# 03_-_SCHEMATIC.net
KiCad netlist of a schematic drawn in Altium Designer
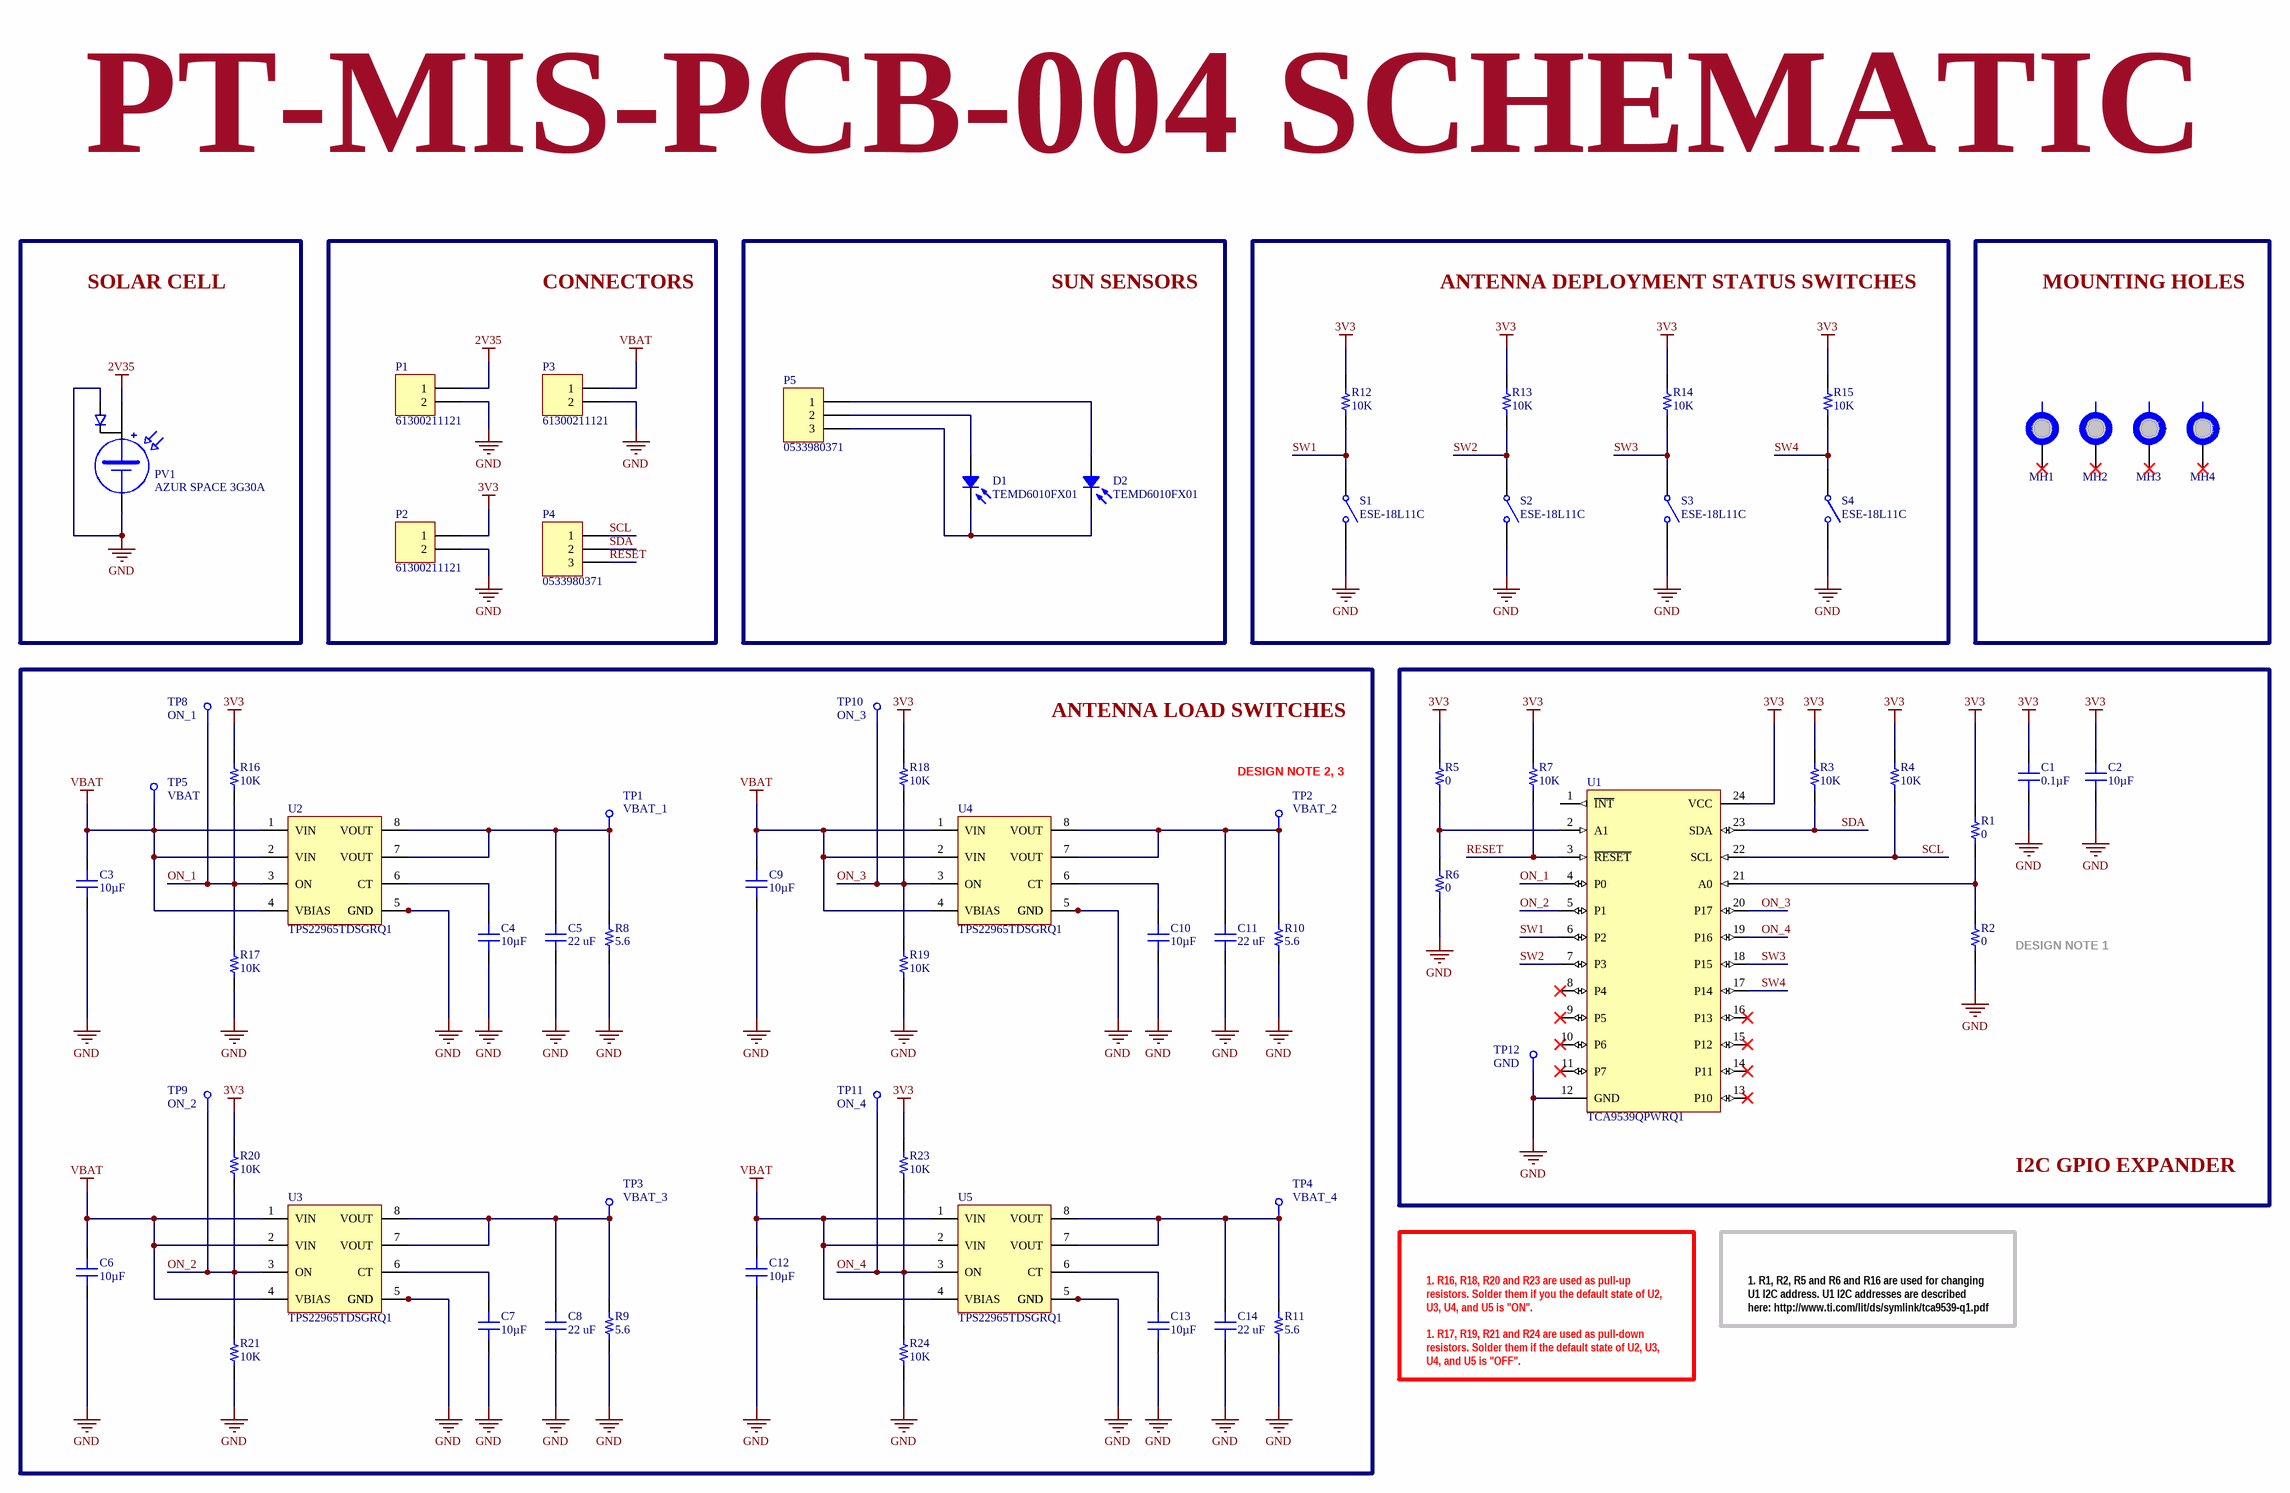
[diagram p0: [03] - SCHEMATIC.SchDoc]

(export (version "E")
  (design (tool "Eeschema 10.0.6"))
  (components
    (comp (ref "C1")
      (value "0.1µF")
      (footprint "CAP 0805/2012")
      (description "Multilayer Ceramic Capacitors MLCC - SMD/SMT 25volts 0.1uF Y5V -20+80%")
      (fields
        (field (name "MANUFACTURER") "KEMET")
        (field (name "MANUFACTURER PART NUMBER") "C0805C104Z3VACTU")
      )
      (libsource (lib "UVG") (part "C0805C104Z3VACTU"))
    )
    (comp (ref "C2")
      (value "LMK212BJ106KG-T")
      (footprint "CAP 0805/2012")
      (description "CAP CER 10UF 10V X5R 0805")
      (fields
        (field (name "MANUFACTURER") "Taiyo Yuden")
        (field (name "PCN PART NUMBER") "X5R, X7R Dielectrics 23/Jan/2008")
        (field (name "CAPACITANCE") "10µF")
      )
      (libsource (lib "UVG") (part "LMK212BJ106KG-T"))
    )
    (comp (ref "C3")
      (value "LMK212BJ106KG-T")
      (footprint "CAP 0805/2012")
      (description "CAP CER 10UF 10V X5R 0805")
      (fields
        (field (name "MANUFACTURER") "Taiyo Yuden")
        (field (name "PCN PART NUMBER") "X5R, X7R Dielectrics 23/Jan/2008")
        (field (name "CAPACITANCE") "10µF")
      )
      (libsource (lib "UVG") (part "LMK212BJ106KG-T"))
    )
    (comp (ref "C4")
      (value "LMK212BJ106KG-T")
      (footprint "CAP 0805/2012")
      (description "CAP CER 10UF 10V X5R 0805")
      (fields
        (field (name "MANUFACTURER") "Taiyo Yuden")
        (field (name "PCN PART NUMBER") "X5R, X7R Dielectrics 23/Jan/2008")
        (field (name "CAPACITANCE") "10µF")
      )
      (libsource (lib "UVG") (part "LMK212BJ106KG-T"))
    )
    (comp (ref "C5")
      (value "GRM21BR61E226ME44L")
      (footprint "CAP 0805/2012")
      (fields
        (field (name "MANUFACTURER") "Murata")
        (field (name "CAPACITANCE") "22 uF")
        (field (name "TOLERANCE") "20 %")
      )
      (libsource (lib "UVG") (part "GRM21BR61E226ME44L"))
    )
    (comp (ref "C6")
      (value "LMK212BJ106KG-T")
      (footprint "CAP 0805/2012")
      (description "CAP CER 10UF 10V X5R 0805")
      (fields
        (field (name "MANUFACTURER") "Taiyo Yuden")
        (field (name "PCN PART NUMBER") "X5R, X7R Dielectrics 23/Jan/2008")
        (field (name "CAPACITANCE") "10µF")
      )
      (libsource (lib "UVG") (part "LMK212BJ106KG-T"))
    )
    (comp (ref "C7")
      (value "LMK212BJ106KG-T")
      (footprint "CAP 0805/2012")
      (description "CAP CER 10UF 10V X5R 0805")
      (fields
        (field (name "MANUFACTURER") "Taiyo Yuden")
        (field (name "PCN PART NUMBER") "X5R, X7R Dielectrics 23/Jan/2008")
        (field (name "CAPACITANCE") "10µF")
      )
      (libsource (lib "UVG") (part "LMK212BJ106KG-T"))
    )
    (comp (ref "C8")
      (value "GRM21BR61E226ME44L")
      (footprint "CAP 0805/2012")
      (fields
        (field (name "MANUFACTURER") "Murata")
        (field (name "CAPACITANCE") "22 uF")
        (field (name "TOLERANCE") "20 %")
      )
      (libsource (lib "UVG") (part "GRM21BR61E226ME44L"))
    )
    (comp (ref "C9")
      (value "LMK212BJ106KG-T")
      (footprint "CAP 0805/2012")
      (description "CAP CER 10UF 10V X5R 0805")
      (fields
        (field (name "MANUFACTURER") "Taiyo Yuden")
        (field (name "PCN PART NUMBER") "X5R, X7R Dielectrics 23/Jan/2008")
        (field (name "CAPACITANCE") "10µF")
      )
      (libsource (lib "UVG") (part "LMK212BJ106KG-T"))
    )
    (comp (ref "C10")
      (value "LMK212BJ106KG-T")
      (footprint "CAP 0805/2012")
      (description "CAP CER 10UF 10V X5R 0805")
      (fields
        (field (name "MANUFACTURER") "Taiyo Yuden")
        (field (name "PCN PART NUMBER") "X5R, X7R Dielectrics 23/Jan/2008")
        (field (name "CAPACITANCE") "10µF")
      )
      (libsource (lib "UVG") (part "LMK212BJ106KG-T"))
    )
    (comp (ref "C11")
      (value "GRM21BR61E226ME44L")
      (footprint "CAP 0805/2012")
      (fields
        (field (name "MANUFACTURER") "Murata")
        (field (name "CAPACITANCE") "22 uF")
        (field (name "TOLERANCE") "20 %")
      )
      (libsource (lib "UVG") (part "GRM21BR61E226ME44L"))
    )
    (comp (ref "C12")
      (value "LMK212BJ106KG-T")
      (footprint "CAP 0805/2012")
      (description "CAP CER 10UF 10V X5R 0805")
      (fields
        (field (name "MANUFACTURER") "Taiyo Yuden")
        (field (name "PCN PART NUMBER") "X5R, X7R Dielectrics 23/Jan/2008")
        (field (name "CAPACITANCE") "10µF")
      )
      (libsource (lib "UVG") (part "LMK212BJ106KG-T"))
    )
    (comp (ref "C13")
      (value "LMK212BJ106KG-T")
      (footprint "CAP 0805/2012")
      (description "CAP CER 10UF 10V X5R 0805")
      (fields
        (field (name "MANUFACTURER") "Taiyo Yuden")
        (field (name "PCN PART NUMBER") "X5R, X7R Dielectrics 23/Jan/2008")
        (field (name "CAPACITANCE") "10µF")
      )
      (libsource (lib "UVG") (part "LMK212BJ106KG-T"))
    )
    (comp (ref "C14")
      (value "GRM21BR61E226ME44L")
      (footprint "CAP 0805/2012")
      (fields
        (field (name "MANUFACTURER") "Murata")
        (field (name "CAPACITANCE") "22 uF")
        (field (name "TOLERANCE") "20 %")
      )
      (libsource (lib "UVG") (part "GRM21BR61E226ME44L"))
    )
    (comp (ref "D1")
      (value "TEMD6010FX01")
      (footprint "TEMD6010FX01")
      (description "Ambient Light Sensor")
      (fields (field (name "MANUFACTURER") "Vishay Semiconductors"))
      (libsource (lib "UVG") (part "TEMD6010FX01"))
    )
    (comp (ref "D2")
      (value "TEMD6010FX01")
      (footprint "TEMD6010FX01")
      (description "Ambient Light Sensor")
      (fields (field (name "MANUFACTURER") "Vishay Semiconductors"))
      (libsource (lib "UVG") (part "TEMD6010FX01"))
    )
    (comp (ref "MH1")
      (value "MH_3.8MMNC_2.5MMD")
      (footprint "MH_3.8MMNC_2.5MMD_NON_COPPER_NPTH")
      (description "Mounting Hole 3.8mm Diameter (Non Copper), 2.5mm Drill NPTH")
      (libsource (lib "UVG") (part "MH_3.8MMNC_2MMD"))
    )
    (comp (ref "MH2")
      (value "MH_3.8MMNC_2.5MMD")
      (footprint "MH_3.8MMNC_2.5MMD_NON_COPPER_NPTH")
      (description "Mounting Hole 3.8mm Diameter (Non Copper), 2.5mm Drill NPTH")
      (libsource (lib "UVG") (part "MH_3.8MMNC_2MMD"))
    )
    (comp (ref "MH3")
      (value "MH_3.8MMNC_2.5MMD")
      (footprint "MH_3.8MMNC_2.5MMD_NON_COPPER_NPTH")
      (description "Mounting Hole 3.8mm Diameter (Non Copper), 2.5mm Drill NPTH")
      (libsource (lib "UVG") (part "MH_3.8MMNC_2MMD"))
    )
    (comp (ref "MH4")
      (value "MH_3.8MMNC_2.5MMD")
      (footprint "MH_3.8MMNC_2.5MMD_NON_COPPER_NPTH")
      (description "Mounting Hole 3.8mm Diameter (Non Copper), 2.5mm Drill NPTH")
      (libsource (lib "UVG") (part "MH_3.8MMNC_2MMD"))
    )
    (comp (ref "P1")
      (value "61300211121")
      (footprint "61300211121")
      (description "Headers & Wire Housings WR-PHD 2.54mm Header 2P THT")
      (fields (field (name "MANUFACTURER") "Wurth Electronics"))
      (libsource (lib "UVG") (part "61300211121"))
    )
    (comp (ref "P2")
      (value "61300211121")
      (footprint "61300211121")
      (description "Headers & Wire Housings WR-PHD 2.54mm Header 2P THT")
      (fields (field (name "MANUFACTURER") "Wurth Electronics"))
      (libsource (lib "UVG") (part "61300211121"))
    )
    (comp (ref "P3")
      (value "61300211121")
      (footprint "61300211121")
      (description "Headers & Wire Housings WR-PHD 2.54mm Header 2P THT")
      (fields (field (name "MANUFACTURER") "Wurth Electronics"))
      (libsource (lib "UVG") (part "61300211121"))
    )
    (comp (ref "P4")
      (value "0533980371")
      (footprint "0533980371")
      (description "3 Positions Header, Shrouded Connector 0.049\" (1.25mm) Surface Mount, Vertical Tin")
      (fields (field (name "MANUFACTURER") "Molex"))
      (libsource (lib "UVG") (part "0533980371"))
    )
    (comp (ref "P5")
      (value "0533980371")
      (footprint "0533980371")
      (description "3 Positions Header, Shrouded Connector 0.049\" (1.25mm) Surface Mount, Vertical Tin")
      (fields (field (name "MANUFACTURER") "Molex"))
      (libsource (lib "UVG") (part "0533980371"))
    )
    (comp (ref "PV1")
      (value "AZUR SPACE 3G30A")
      (footprint "AZUR SPACE 3G30A")
      (description "30% Triple Junction GaAs Solar Cell Assembly")
      (libsource (lib "UVG") (part "AZUR SPACE 3G30A"))
    )
    (comp (ref "R1")
      (value "0")
      (footprint "RES 0805/2012")
      (description "YAGEO         RC0805JR-070RL             RES, THICK FILM, 0R, 0.125W, 0805")
      (fields
        (field (name "MANUFACTURER") "Yageo")
        (field (name "MANUFACTURER PART NUMBER") "RC0805JR-070RL")
      )
      (libsource (lib "UVG") (part "RC0805JR-070RL"))
    )
    (comp (ref "R2")
      (value "0")
      (footprint "RES 0805/2012")
      (description "YAGEO         RC0805JR-070RL             RES, THICK FILM, 0R, 0.125W, 0805")
      (fields
        (field (name "MANUFACTURER") "Yageo")
        (field (name "MANUFACTURER PART NUMBER") "RC0805JR-070RL")
      )
      (libsource (lib "UVG") (part "RC0805JR-070RL"))
    )
    (comp (ref "R3")
      (value "10K")
      (footprint "RES 0805/2012")
      (description "RES SMD 10K OHM 1% 1/8W 0805")
      (fields
        (field (name "MANUFACTURER") "Yageo")
        (field (name "MANUFACTURER PART NUMBER") "RC0805FR-0710KL")
      )
      (libsource (lib "UVG") (part "RC0805FR-0710KL"))
    )
    (comp (ref "R4")
      (value "10K")
      (footprint "RES 0805/2012")
      (description "RES SMD 10K OHM 1% 1/8W 0805")
      (fields
        (field (name "MANUFACTURER") "Yageo")
        (field (name "MANUFACTURER PART NUMBER") "RC0805FR-0710KL")
      )
      (libsource (lib "UVG") (part "RC0805FR-0710KL"))
    )
    (comp (ref "R5")
      (value "0")
      (footprint "RES 0805/2012")
      (description "YAGEO         RC0805JR-070RL             RES, THICK FILM, 0R, 0.125W, 0805")
      (fields
        (field (name "MANUFACTURER") "Yageo")
        (field (name "MANUFACTURER PART NUMBER") "RC0805JR-070RL")
      )
      (libsource (lib "UVG") (part "RC0805JR-070RL"))
    )
    (comp (ref "R6")
      (value "0")
      (footprint "RES 0805/2012")
      (description "YAGEO         RC0805JR-070RL             RES, THICK FILM, 0R, 0.125W, 0805")
      (fields
        (field (name "MANUFACTURER") "Yageo")
        (field (name "MANUFACTURER PART NUMBER") "RC0805JR-070RL")
      )
      (libsource (lib "UVG") (part "RC0805JR-070RL"))
    )
    (comp (ref "R7")
      (value "10K")
      (footprint "RES 0805/2012")
      (description "RES SMD 10K OHM 1% 1/8W 0805")
      (fields
        (field (name "MANUFACTURER") "Yageo")
        (field (name "MANUFACTURER PART NUMBER") "RC0805FR-0710KL")
      )
      (libsource (lib "UVG") (part "RC0805FR-0710KL"))
    )
    (comp (ref "R8")
      (value "5.6")
      (footprint "MFR50SFTE52-5R6")
      (description "Metal Film Resistors - Through Hole 5.6 OHM 1/2W 1%")
      (fields
        (field (name "MANUFACTURER") "Yageo")
        (field (name "MANUFACTURER PART NUMBER") "MFR50SFTE52-5R6")
      )
      (libsource (lib "UVG") (part "MFR50SFTE52-5R6"))
    )
    (comp (ref "R9")
      (value "5.6")
      (footprint "MFR50SFTE52-5R6")
      (description "Metal Film Resistors - Through Hole 5.6 OHM 1/2W 1%")
      (fields
        (field (name "MANUFACTURER") "Yageo")
        (field (name "MANUFACTURER PART NUMBER") "MFR50SFTE52-5R6")
      )
      (libsource (lib "UVG") (part "MFR50SFTE52-5R6"))
    )
    (comp (ref "R10")
      (value "5.6")
      (footprint "MFR50SFTE52-5R6")
      (description "Metal Film Resistors - Through Hole 5.6 OHM 1/2W 1%")
      (fields
        (field (name "MANUFACTURER") "Yageo")
        (field (name "MANUFACTURER PART NUMBER") "MFR50SFTE52-5R6")
      )
      (libsource (lib "UVG") (part "MFR50SFTE52-5R6"))
    )
    (comp (ref "R11")
      (value "5.6")
      (footprint "MFR50SFTE52-5R6")
      (description "Metal Film Resistors - Through Hole 5.6 OHM 1/2W 1%")
      (fields
        (field (name "MANUFACTURER") "Yageo")
        (field (name "MANUFACTURER PART NUMBER") "MFR50SFTE52-5R6")
      )
      (libsource (lib "UVG") (part "MFR50SFTE52-5R6"))
    )
    (comp (ref "R12")
      (value "10K")
      (footprint "RES 0805/2012")
      (description "RES SMD 10K OHM 1% 1/8W 0805")
      (fields
        (field (name "MANUFACTURER") "Yageo")
        (field (name "MANUFACTURER PART NUMBER") "RC0805FR-0710KL")
      )
      (libsource (lib "UVG") (part "RC0805FR-0710KL"))
    )
    (comp (ref "R13")
      (value "10K")
      (footprint "RES 0805/2012")
      (description "RES SMD 10K OHM 1% 1/8W 0805")
      (fields
        (field (name "MANUFACTURER") "Yageo")
        (field (name "MANUFACTURER PART NUMBER") "RC0805FR-0710KL")
      )
      (libsource (lib "UVG") (part "RC0805FR-0710KL"))
    )
    (comp (ref "R14")
      (value "10K")
      (footprint "RES 0805/2012")
      (description "RES SMD 10K OHM 1% 1/8W 0805")
      (fields
        (field (name "MANUFACTURER") "Yageo")
        (field (name "MANUFACTURER PART NUMBER") "RC0805FR-0710KL")
      )
      (libsource (lib "UVG") (part "RC0805FR-0710KL"))
    )
    (comp (ref "R15")
      (value "10K")
      (footprint "RES 0805/2012")
      (description "RES SMD 10K OHM 1% 1/8W 0805")
      (fields
        (field (name "MANUFACTURER") "Yageo")
        (field (name "MANUFACTURER PART NUMBER") "RC0805FR-0710KL")
      )
      (libsource (lib "UVG") (part "RC0805FR-0710KL"))
    )
    (comp (ref "R16")
      (value "10K")
      (footprint "RES 0805/2012")
      (description "RES SMD 10K OHM 1% 1/8W 0805")
      (fields
        (field (name "MANUFACTURER") "Yageo")
        (field (name "MANUFACTURER PART NUMBER") "RC0805FR-0710KL")
      )
      (libsource (lib "UVG") (part "RC0805FR-0710KL"))
    )
    (comp (ref "R17")
      (value "10K")
      (footprint "RES 0805/2012")
      (description "RES SMD 10K OHM 1% 1/8W 0805")
      (fields
        (field (name "MANUFACTURER") "Yageo")
        (field (name "MANUFACTURER PART NUMBER") "RC0805FR-0710KL")
      )
      (libsource (lib "UVG") (part "RC0805FR-0710KL"))
    )
    (comp (ref "R18")
      (value "10K")
      (footprint "RES 0805/2012")
      (description "RES SMD 10K OHM 1% 1/8W 0805")
      (fields
        (field (name "MANUFACTURER") "Yageo")
        (field (name "MANUFACTURER PART NUMBER") "RC0805FR-0710KL")
      )
      (libsource (lib "UVG") (part "RC0805FR-0710KL"))
    )
    (comp (ref "R19")
      (value "10K")
      (footprint "RES 0805/2012")
      (description "RES SMD 10K OHM 1% 1/8W 0805")
      (fields
        (field (name "MANUFACTURER") "Yageo")
        (field (name "MANUFACTURER PART NUMBER") "RC0805FR-0710KL")
      )
      (libsource (lib "UVG") (part "RC0805FR-0710KL"))
    )
    (comp (ref "R20")
      (value "10K")
      (footprint "RES 0805/2012")
      (description "RES SMD 10K OHM 1% 1/8W 0805")
      (fields
        (field (name "MANUFACTURER") "Yageo")
        (field (name "MANUFACTURER PART NUMBER") "RC0805FR-0710KL")
      )
      (libsource (lib "UVG") (part "RC0805FR-0710KL"))
    )
    (comp (ref "R21")
      (value "10K")
      (footprint "RES 0805/2012")
      (description "RES SMD 10K OHM 1% 1/8W 0805")
      (fields
        (field (name "MANUFACTURER") "Yageo")
        (field (name "MANUFACTURER PART NUMBER") "RC0805FR-0710KL")
      )
      (libsource (lib "UVG") (part "RC0805FR-0710KL"))
    )
    (comp (ref "R23")
      (value "10K")
      (footprint "RES 0805/2012")
      (description "RES SMD 10K OHM 1% 1/8W 0805")
      (fields
        (field (name "MANUFACTURER") "Yageo")
        (field (name "MANUFACTURER PART NUMBER") "RC0805FR-0710KL")
      )
      (libsource (lib "UVG") (part "RC0805FR-0710KL"))
    )
    (comp (ref "R24")
      (value "10K")
      (footprint "RES 0805/2012")
      (description "RES SMD 10K OHM 1% 1/8W 0805")
      (fields
        (field (name "MANUFACTURER") "Yageo")
        (field (name "MANUFACTURER PART NUMBER") "RC0805FR-0710KL")
      )
      (libsource (lib "UVG") (part "RC0805FR-0710KL"))
    )
    (comp (ref "S1")
      (value "ESE-18L11C")
      (footprint "ESE-18L11C")
      (description "Detector switch,SMT,SPNO,1HL,no boss")
      (fields (field (name "MANUFACTURER") "Panasonic ECG"))
      (libsource (lib "UVG") (part "ESE-18L11C"))
    )
    (comp (ref "S2")
      (value "ESE-18L11C")
      (footprint "ESE-18L11C")
      (description "Detector switch,SMT,SPNO,1HL,no boss")
      (fields (field (name "MANUFACTURER") "Panasonic ECG"))
      (libsource (lib "UVG") (part "ESE-18L11C"))
    )
    (comp (ref "S3")
      (value "ESE-18L11C")
      (footprint "ESE-18L11C")
      (description "Detector switch,SMT,SPNO,1HL,no boss")
      (fields (field (name "MANUFACTURER") "Panasonic ECG"))
      (libsource (lib "UVG") (part "ESE-18L11C"))
    )
    (comp (ref "S4")
      (value "ESE-18L11C")
      (footprint "ESE-18L11C")
      (description "Detector switch,SMT,SPNO,1HL,no boss")
      (fields (field (name "MANUFACTURER") "Panasonic ECG"))
      (libsource (lib "UVG") (part "ESE-18L11C"))
    )
    (comp (ref "TP1") (value "Testpoint") (footprint "Testpoint") (libsource (lib "UVG") (part "Testpoint")))
    (comp (ref "TP2") (value "Testpoint") (footprint "Testpoint") (libsource (lib "UVG") (part "Testpoint")))
    (comp (ref "TP3") (value "Testpoint") (footprint "Testpoint") (libsource (lib "UVG") (part "Testpoint")))
    (comp (ref "TP4") (value "Testpoint") (footprint "Testpoint") (libsource (lib "UVG") (part "Testpoint")))
    (comp (ref "TP5") (value "Testpoint") (footprint "Testpoint") (libsource (lib "UVG") (part "Testpoint")))
    (comp (ref "TP8") (value "ON_1") (footprint "Testpoint") (libsource (lib "UVG") (part "Testpoint")))
    (comp (ref "TP9") (value "ON_2") (footprint "Testpoint") (libsource (lib "UVG") (part "Testpoint")))
    (comp (ref "TP10") (value "ON_3") (footprint "Testpoint") (libsource (lib "UVG") (part "Testpoint")))
    (comp (ref "TP11") (value "ON_4") (footprint "Testpoint") (libsource (lib "UVG") (part "Testpoint")))
    (comp (ref "TP12") (value "GND") (footprint "Testpoint") (libsource (lib "UVG") (part "Testpoint")))
    (comp (ref "U1")
      (value "TCA9539QPWRQ1")
      (footprint "TSOP65P640X120-24N")
      (fields (field (name "MANUFACTURER") "Texas Instruments"))
      (libsource (lib "UVG") (part "TCA9539QPWRQ1"))
    )
    (comp (ref "U2")
      (value "TPS22965TDSGRQ1")
      (footprint "SON50P200X80_HS-9N")
      (description "IC LOAD SWITCH 6A 8WSON")
      (fields (field (name "MANUFACTURER") "Texas Instruments"))
      (libsource (lib "UVG") (part "TPS22965TDSGRQ1"))
    )
    (comp (ref "U3")
      (value "TPS22965TDSGRQ1")
      (footprint "SON50P200X80_HS-9N")
      (description "IC LOAD SWITCH 6A 8WSON")
      (fields (field (name "MANUFACTURER") "Texas Instruments"))
      (libsource (lib "UVG") (part "TPS22965TDSGRQ1"))
    )
    (comp (ref "U4")
      (value "TPS22965TDSGRQ1")
      (footprint "SON50P200X80_HS-9N")
      (description "IC LOAD SWITCH 6A 8WSON")
      (fields (field (name "MANUFACTURER") "Texas Instruments"))
      (libsource (lib "UVG") (part "TPS22965TDSGRQ1"))
    )
    (comp (ref "U5")
      (value "TPS22965TDSGRQ1")
      (footprint "SON50P200X80_HS-9N")
      (description "IC LOAD SWITCH 6A 8WSON")
      (fields (field (name "MANUFACTURER") "Texas Instruments"))
      (libsource (lib "UVG") (part "TPS22965TDSGRQ1"))
    )
  )
  (nets
    (net (code "1") (name "/ON_1") (class "Default")
      (node (ref "R16") (pin "1") (pinfunction "1_1") (pintype "passive"))
      (node (ref "R17") (pin "2") (pinfunction "2_2") (pintype "passive"))
      (node (ref "TP8") (pin "1") (pinfunction "1_1") (pintype "passive"))
      (node (ref "U1") (pin "4") (pinfunction "P0_4") (pintype "bidirectional"))
      (node (ref "U2") (pin "3") (pinfunction "ON_3") (pintype "passive"))
    )
    (net (code "2") (name "/ON_2") (class "Default")
      (node (ref "R20") (pin "1") (pinfunction "1_1") (pintype "passive"))
      (node (ref "R21") (pin "2") (pinfunction "2_2") (pintype "passive"))
      (node (ref "TP9") (pin "1") (pinfunction "1_1") (pintype "passive"))
      (node (ref "U1") (pin "5") (pinfunction "P1_5") (pintype "bidirectional"))
      (node (ref "U3") (pin "3") (pinfunction "ON_3") (pintype "passive"))
    )
    (net (code "3") (name "/ON_3") (class "Default")
      (node (ref "R18") (pin "1") (pinfunction "1_1") (pintype "passive"))
      (node (ref "R19") (pin "2") (pinfunction "2_2") (pintype "passive"))
      (node (ref "TP10") (pin "1") (pinfunction "1_1") (pintype "passive"))
      (node (ref "U1") (pin "20") (pinfunction "P17_20") (pintype "bidirectional"))
      (node (ref "U4") (pin "3") (pinfunction "ON_3") (pintype "passive"))
    )
    (net (code "4") (name "/ON_4") (class "Default")
      (node (ref "R23") (pin "1") (pinfunction "1_1") (pintype "passive"))
      (node (ref "R24") (pin "2") (pinfunction "2_2") (pintype "passive"))
      (node (ref "TP11") (pin "1") (pinfunction "1_1") (pintype "passive"))
      (node (ref "U1") (pin "19") (pinfunction "P16_19") (pintype "bidirectional"))
      (node (ref "U5") (pin "3") (pinfunction "ON_3") (pintype "passive"))
    )
    (net (code "5") (name "/RESET") (class "Default")
      (node (ref "P4") (pin "3") (pinfunction "3_3") (pintype "passive"))
      (node (ref "R7") (pin "1") (pinfunction "1_1") (pintype "passive"))
      (node (ref "U1") (pin "3") (pinfunction "~{RESET}_3") (pintype "input"))
    )
    (net (code "6") (name "/SCL") (class "Default")
      (node (ref "P4") (pin "1") (pinfunction "1_1") (pintype "passive"))
      (node (ref "R4") (pin "1") (pinfunction "1_1") (pintype "passive"))
      (node (ref "U1") (pin "22") (pinfunction "SCL_22") (pintype "input"))
    )
    (net (code "7") (name "/SDA") (class "Default")
      (node (ref "P4") (pin "2") (pinfunction "2_2") (pintype "passive"))
      (node (ref "R3") (pin "1") (pinfunction "1_1") (pintype "passive"))
      (node (ref "U1") (pin "23") (pinfunction "SDA_23") (pintype "bidirectional"))
    )
    (net (code "8") (name "/SW1") (class "Default")
      (node (ref "R12") (pin "1") (pinfunction "1_1") (pintype "passive"))
      (node (ref "S1") (pin "1") (pinfunction "COMMON_1") (pintype "passive"))
      (node (ref "U1") (pin "6") (pinfunction "P2_6") (pintype "bidirectional"))
    )
    (net (code "9") (name "/SW2") (class "Default")
      (node (ref "R13") (pin "1") (pinfunction "1_1") (pintype "passive"))
      (node (ref "S2") (pin "1") (pinfunction "COMMON_1") (pintype "passive"))
      (node (ref "U1") (pin "7") (pinfunction "P3_7") (pintype "bidirectional"))
    )
    (net (code "10") (name "/SW3") (class "Default")
      (node (ref "R14") (pin "1") (pinfunction "1_1") (pintype "passive"))
      (node (ref "S3") (pin "1") (pinfunction "COMMON_1") (pintype "passive"))
      (node (ref "U1") (pin "18") (pinfunction "P15_18") (pintype "bidirectional"))
    )
    (net (code "11") (name "/SW4") (class "Default")
      (node (ref "R15") (pin "1") (pinfunction "1_1") (pintype "passive"))
      (node (ref "S4") (pin "1") (pinfunction "COMMON_1") (pintype "passive"))
      (node (ref "U1") (pin "17") (pinfunction "P14_17") (pintype "bidirectional"))
    )
    (net (code "12") (name "2V35") (class "Default")
      (node (ref "P1") (pin "1") (pinfunction "1_1") (pintype "passive"))
      (node (ref "PV1") (pin "1") (pinfunction "1_1") (pintype "passive"))
    )
    (net (code "13") (name "3V3") (class "Default")
      (node (ref "C1") (pin "2") (pinfunction "2_2") (pintype "passive"))
      (node (ref "C2") (pin "2") (pinfunction "2_2") (pintype "passive"))
      (node (ref "P2") (pin "1") (pinfunction "1_1") (pintype "passive"))
      (node (ref "R1") (pin "2") (pinfunction "2_2") (pintype "passive"))
      (node (ref "R12") (pin "2") (pinfunction "2_2") (pintype "passive"))
      (node (ref "R13") (pin "2") (pinfunction "2_2") (pintype "passive"))
      (node (ref "R14") (pin "2") (pinfunction "2_2") (pintype "passive"))
      (node (ref "R15") (pin "2") (pinfunction "2_2") (pintype "passive"))
      (node (ref "R16") (pin "2") (pinfunction "2_2") (pintype "passive"))
      (node (ref "R18") (pin "2") (pinfunction "2_2") (pintype "passive"))
      (node (ref "R20") (pin "2") (pinfunction "2_2") (pintype "passive"))
      (node (ref "R23") (pin "2") (pinfunction "2_2") (pintype "passive"))
      (node (ref "R3") (pin "2") (pinfunction "2_2") (pintype "passive"))
      (node (ref "R4") (pin "2") (pinfunction "2_2") (pintype "passive"))
      (node (ref "R5") (pin "2") (pinfunction "2_2") (pintype "passive"))
      (node (ref "R7") (pin "2") (pinfunction "2_2") (pintype "passive"))
      (node (ref "U1") (pin "24") (pinfunction "VCC_24") (pintype "power_in"))
    )
    (net (code "14") (name "GND") (class "Default")
      (node (ref "C1") (pin "1") (pinfunction "1_1") (pintype "passive"))
      (node (ref "C10") (pin "2") (pinfunction "2_2") (pintype "passive"))
      (node (ref "C11") (pin "1") (pinfunction "1_1") (pintype "passive"))
      (node (ref "C12") (pin "1") (pinfunction "1_1") (pintype "passive"))
      (node (ref "C13") (pin "2") (pinfunction "2_2") (pintype "passive"))
      (node (ref "C14") (pin "1") (pinfunction "1_1") (pintype "passive"))
      (node (ref "C2") (pin "1") (pinfunction "1_1") (pintype "passive"))
      (node (ref "C3") (pin "1") (pinfunction "1_1") (pintype "passive"))
      (node (ref "C4") (pin "2") (pinfunction "2_2") (pintype "passive"))
      (node (ref "C5") (pin "1") (pinfunction "1_1") (pintype "passive"))
      (node (ref "C6") (pin "1") (pinfunction "1_1") (pintype "passive"))
      (node (ref "C7") (pin "2") (pinfunction "2_2") (pintype "passive"))
      (node (ref "C8") (pin "1") (pinfunction "1_1") (pintype "passive"))
      (node (ref "C9") (pin "1") (pinfunction "1_1") (pintype "passive"))
      (node (ref "P1") (pin "2") (pinfunction "2_2") (pintype "passive"))
      (node (ref "P2") (pin "2") (pinfunction "2_2") (pintype "passive"))
      (node (ref "P3") (pin "2") (pinfunction "2_2") (pintype "passive"))
      (node (ref "PV1") (pin "2") (pinfunction "2_2") (pintype "passive"))
      (node (ref "PV1") (pin "3") (pinfunction "3_3") (pintype "passive"))
      (node (ref "R10") (pin "1") (pinfunction "1_1") (pintype "passive"))
      (node (ref "R11") (pin "1") (pinfunction "1_1") (pintype "passive"))
      (node (ref "R17") (pin "1") (pinfunction "1_1") (pintype "passive"))
      (node (ref "R19") (pin "1") (pinfunction "1_1") (pintype "passive"))
      (node (ref "R2") (pin "1") (pinfunction "1_1") (pintype "passive"))
      (node (ref "R21") (pin "1") (pinfunction "1_1") (pintype "passive"))
      (node (ref "R24") (pin "1") (pinfunction "1_1") (pintype "passive"))
      (node (ref "R6") (pin "1") (pinfunction "1_1") (pintype "passive"))
      (node (ref "R8") (pin "1") (pinfunction "1_1") (pintype "passive"))
      (node (ref "R9") (pin "1") (pinfunction "1_1") (pintype "passive"))
      (node (ref "S1") (pin "2") (pinfunction "NO_2") (pintype "passive"))
      (node (ref "S2") (pin "2") (pinfunction "NO_2") (pintype "passive"))
      (node (ref "S3") (pin "2") (pinfunction "NO_2") (pintype "passive"))
      (node (ref "S4") (pin "2") (pinfunction "NO_2") (pintype "passive"))
      (node (ref "TP12") (pin "1") (pinfunction "1_1") (pintype "passive"))
      (node (ref "U1") (pin "12") (pinfunction "GND_12") (pintype "power_in"))
      (node (ref "U2") (pin "5") (pinfunction "GND_5") (pintype "power_in"))
      (node (ref "U2") (pin "9") (pinfunction "GND_9") (pintype "power_in"))
      (node (ref "U3") (pin "5") (pinfunction "GND_5") (pintype "power_in"))
      (node (ref "U3") (pin "9") (pinfunction "GND_9") (pintype "power_in"))
      (node (ref "U4") (pin "5") (pinfunction "GND_5") (pintype "power_in"))
      (node (ref "U4") (pin "9") (pinfunction "GND_9") (pintype "power_in"))
      (node (ref "U5") (pin "5") (pinfunction "GND_5") (pintype "power_in"))
      (node (ref "U5") (pin "9") (pinfunction "GND_9") (pintype "power_in"))
    )
    (net (code "15") (name "Net-(C5-Pad2)") (class "Default")
      (node (ref "C5") (pin "2") (pinfunction "2_2") (pintype "passive"))
      (node (ref "R8") (pin "2") (pinfunction "2_2") (pintype "passive"))
      (node (ref "TP1") (pin "1") (pinfunction "1_1") (pintype "passive"))
      (node (ref "U2") (pin "7") (pinfunction "VOUT_7") (pintype "power_in"))
      (node (ref "U2") (pin "8") (pinfunction "VOUT_8") (pintype "power_in"))
    )
    (net (code "16") (name "Net-(C8-Pad2)") (class "Default")
      (node (ref "C8") (pin "2") (pinfunction "2_2") (pintype "passive"))
      (node (ref "R9") (pin "2") (pinfunction "2_2") (pintype "passive"))
      (node (ref "TP3") (pin "1") (pinfunction "1_1") (pintype "passive"))
      (node (ref "U3") (pin "7") (pinfunction "VOUT_7") (pintype "power_in"))
      (node (ref "U3") (pin "8") (pinfunction "VOUT_8") (pintype "power_in"))
    )
    (net (code "17") (name "Net-(C11-Pad2)") (class "Default")
      (node (ref "C11") (pin "2") (pinfunction "2_2") (pintype "passive"))
      (node (ref "R10") (pin "2") (pinfunction "2_2") (pintype "passive"))
      (node (ref "TP2") (pin "1") (pinfunction "1_1") (pintype "passive"))
      (node (ref "U4") (pin "7") (pinfunction "VOUT_7") (pintype "power_in"))
      (node (ref "U4") (pin "8") (pinfunction "VOUT_8") (pintype "power_in"))
    )
    (net (code "18") (name "Net-(C14-Pad2)") (class "Default")
      (node (ref "C14") (pin "2") (pinfunction "2_2") (pintype "passive"))
      (node (ref "R11") (pin "2") (pinfunction "2_2") (pintype "passive"))
      (node (ref "TP4") (pin "1") (pinfunction "1_1") (pintype "passive"))
      (node (ref "U5") (pin "7") (pinfunction "VOUT_7") (pintype "power_in"))
      (node (ref "U5") (pin "8") (pinfunction "VOUT_8") (pintype "power_in"))
    )
    (net (code "19") (name "Net-(D1-Pad1)") (class "Default")
      (node (ref "D1") (pin "1") (pinfunction "1_1") (pintype "passive"))
      (node (ref "P5") (pin "2") (pinfunction "2_2") (pintype "passive"))
    )
    (net (code "20") (name "Net-(D1-Pad2)") (class "Default")
      (node (ref "D1") (pin "2") (pinfunction "2_2") (pintype "passive"))
      (node (ref "D2") (pin "2") (pinfunction "2_2") (pintype "passive"))
      (node (ref "P5") (pin "3") (pinfunction "3_3") (pintype "passive"))
    )
    (net (code "21") (name "Net-(D2-Pad1)") (class "Default")
      (node (ref "D2") (pin "1") (pinfunction "1_1") (pintype "passive"))
      (node (ref "P5") (pin "1") (pinfunction "1_1") (pintype "passive"))
    )
    (net (code "22") (name "Net-(U1-A0)") (class "Default")
      (node (ref "R1") (pin "1") (pinfunction "1_1") (pintype "passive"))
      (node (ref "R2") (pin "2") (pinfunction "2_2") (pintype "passive"))
      (node (ref "U1") (pin "21") (pinfunction "A0_21") (pintype "input"))
    )
    (net (code "23") (name "Net-(U1-A1)") (class "Default")
      (node (ref "R5") (pin "1") (pinfunction "1_1") (pintype "passive"))
      (node (ref "R6") (pin "2") (pinfunction "2_2") (pintype "passive"))
      (node (ref "U1") (pin "2") (pinfunction "A1_2") (pintype "input"))
    )
    (net (code "24") (name "Net-(U2-CT)") (class "Default")
      (node (ref "C4") (pin "1") (pinfunction "1_1") (pintype "passive"))
      (node (ref "U2") (pin "6") (pinfunction "CT_6") (pintype "passive"))
    )
    (net (code "25") (name "Net-(U3-CT)") (class "Default")
      (node (ref "C7") (pin "1") (pinfunction "1_1") (pintype "passive"))
      (node (ref "U3") (pin "6") (pinfunction "CT_6") (pintype "passive"))
    )
    (net (code "26") (name "Net-(U4-CT)") (class "Default")
      (node (ref "C10") (pin "1") (pinfunction "1_1") (pintype "passive"))
      (node (ref "U4") (pin "6") (pinfunction "CT_6") (pintype "passive"))
    )
    (net (code "27") (name "Net-(U5-CT)") (class "Default")
      (node (ref "C13") (pin "1") (pinfunction "1_1") (pintype "passive"))
      (node (ref "U5") (pin "6") (pinfunction "CT_6") (pintype "passive"))
    )
    (net (code "28") (name "VBAT") (class "Default")
      (node (ref "C12") (pin "2") (pinfunction "2_2") (pintype "passive"))
      (node (ref "C3") (pin "2") (pinfunction "2_2") (pintype "passive"))
      (node (ref "C6") (pin "2") (pinfunction "2_2") (pintype "passive"))
      (node (ref "C9") (pin "2") (pinfunction "2_2") (pintype "passive"))
      (node (ref "P3") (pin "1") (pinfunction "1_1") (pintype "passive"))
      (node (ref "TP5") (pin "1") (pinfunction "1_1") (pintype "passive"))
      (node (ref "U2") (pin "1") (pinfunction "VIN_1") (pintype "power_in"))
      (node (ref "U2") (pin "2") (pinfunction "VIN_2") (pintype "passive"))
      (node (ref "U2") (pin "4") (pinfunction "VBIAS_4") (pintype "passive"))
      (node (ref "U3") (pin "1") (pinfunction "VIN_1") (pintype "power_in"))
      (node (ref "U3") (pin "2") (pinfunction "VIN_2") (pintype "passive"))
      (node (ref "U3") (pin "4") (pinfunction "VBIAS_4") (pintype "passive"))
      (node (ref "U4") (pin "1") (pinfunction "VIN_1") (pintype "power_in"))
      (node (ref "U4") (pin "2") (pinfunction "VIN_2") (pintype "passive"))
      (node (ref "U4") (pin "4") (pinfunction "VBIAS_4") (pintype "passive"))
      (node (ref "U5") (pin "1") (pinfunction "VIN_1") (pintype "power_in"))
      (node (ref "U5") (pin "2") (pinfunction "VIN_2") (pintype "passive"))
      (node (ref "U5") (pin "4") (pinfunction "VBIAS_4") (pintype "passive"))
    )
    (net (code "29") (name "unconnected-(MH1-Pad1)") (class "Default")
      (node (ref "MH1") (pin "1") (pinfunction "1_1") (pintype "passive"))
    )
    (net (code "30") (name "unconnected-(MH2-Pad1)") (class "Default")
      (node (ref "MH2") (pin "1") (pinfunction "1_1") (pintype "passive"))
    )
    (net (code "31") (name "unconnected-(MH3-Pad1)") (class "Default")
      (node (ref "MH3") (pin "1") (pinfunction "1_1") (pintype "passive"))
    )
    (net (code "32") (name "unconnected-(MH4-Pad1)") (class "Default")
      (node (ref "MH4") (pin "1") (pinfunction "1_1") (pintype "passive"))
    )
    (net (code "33") (name "unconnected-(U1-P4-Pad8)") (class "Default")
      (node (ref "U1") (pin "8") (pinfunction "P4_8") (pintype "bidirectional+no_connect"))
    )
    (net (code "34") (name "unconnected-(U1-P5-Pad9)") (class "Default")
      (node (ref "U1") (pin "9") (pinfunction "P5_9") (pintype "bidirectional+no_connect"))
    )
    (net (code "35") (name "unconnected-(U1-P6-Pad10)") (class "Default")
      (node (ref "U1") (pin "10") (pinfunction "P6_10") (pintype "bidirectional+no_connect"))
    )
    (net (code "36") (name "unconnected-(U1-P7-Pad11)") (class "Default")
      (node (ref "U1") (pin "11") (pinfunction "P7_11") (pintype "bidirectional+no_connect"))
    )
    (net (code "37") (name "unconnected-(U1-P10-Pad13)") (class "Default")
      (node (ref "U1") (pin "13") (pinfunction "P10_13") (pintype "bidirectional+no_connect"))
    )
    (net (code "38") (name "unconnected-(U1-P11-Pad14)") (class "Default")
      (node (ref "U1") (pin "14") (pinfunction "P11_14") (pintype "bidirectional+no_connect"))
    )
    (net (code "39") (name "unconnected-(U1-P12-Pad15)") (class "Default")
      (node (ref "U1") (pin "15") (pinfunction "P12_15") (pintype "bidirectional+no_connect"))
    )
    (net (code "40") (name "unconnected-(U1-P13-Pad16)") (class "Default")
      (node (ref "U1") (pin "16") (pinfunction "P13_16") (pintype "bidirectional+no_connect"))
    )
    (net (code "41") (name "unconnected-(U1-~{INT}-Pad1)") (class "Default")
      (node (ref "U1") (pin "1") (pinfunction "~{INT}_1") (pintype "output"))
    )
  )
)
